# lipolski-power.net
KiCad netlist of a schematic drawn in EAGLE
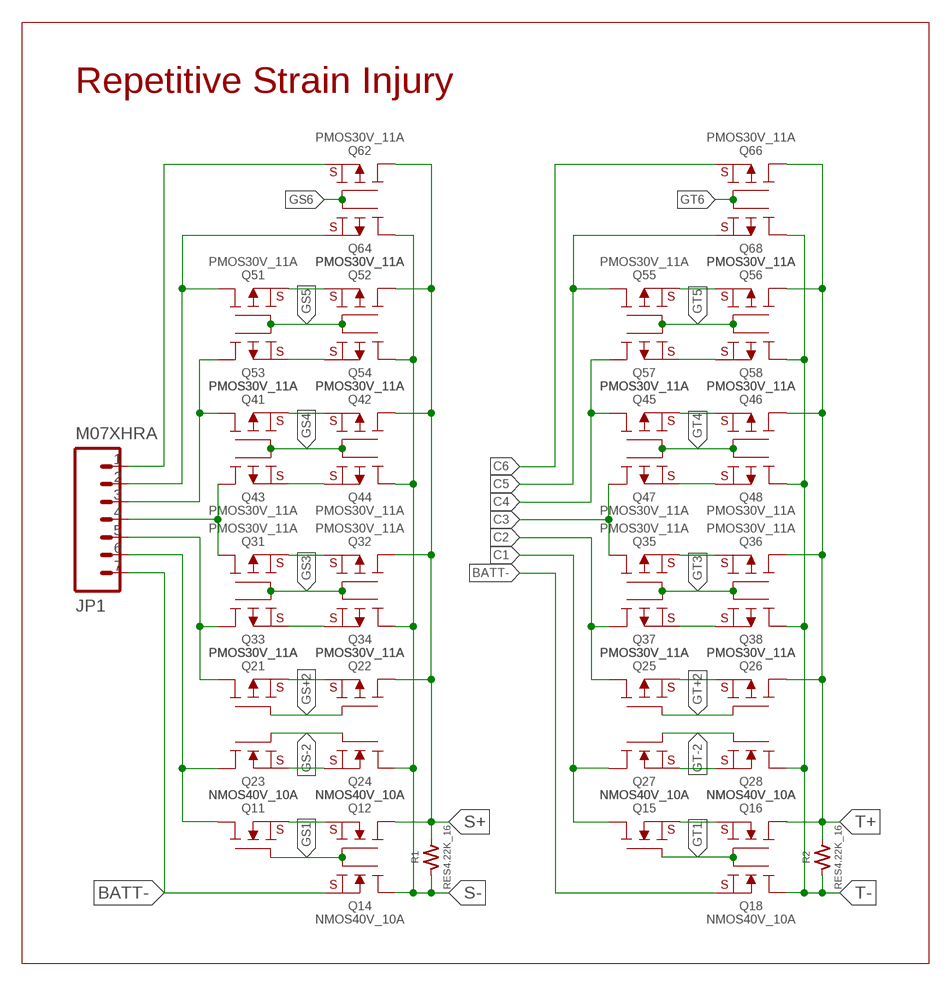
[diagram p0: schematic, sheet 1, part 1 of 2]
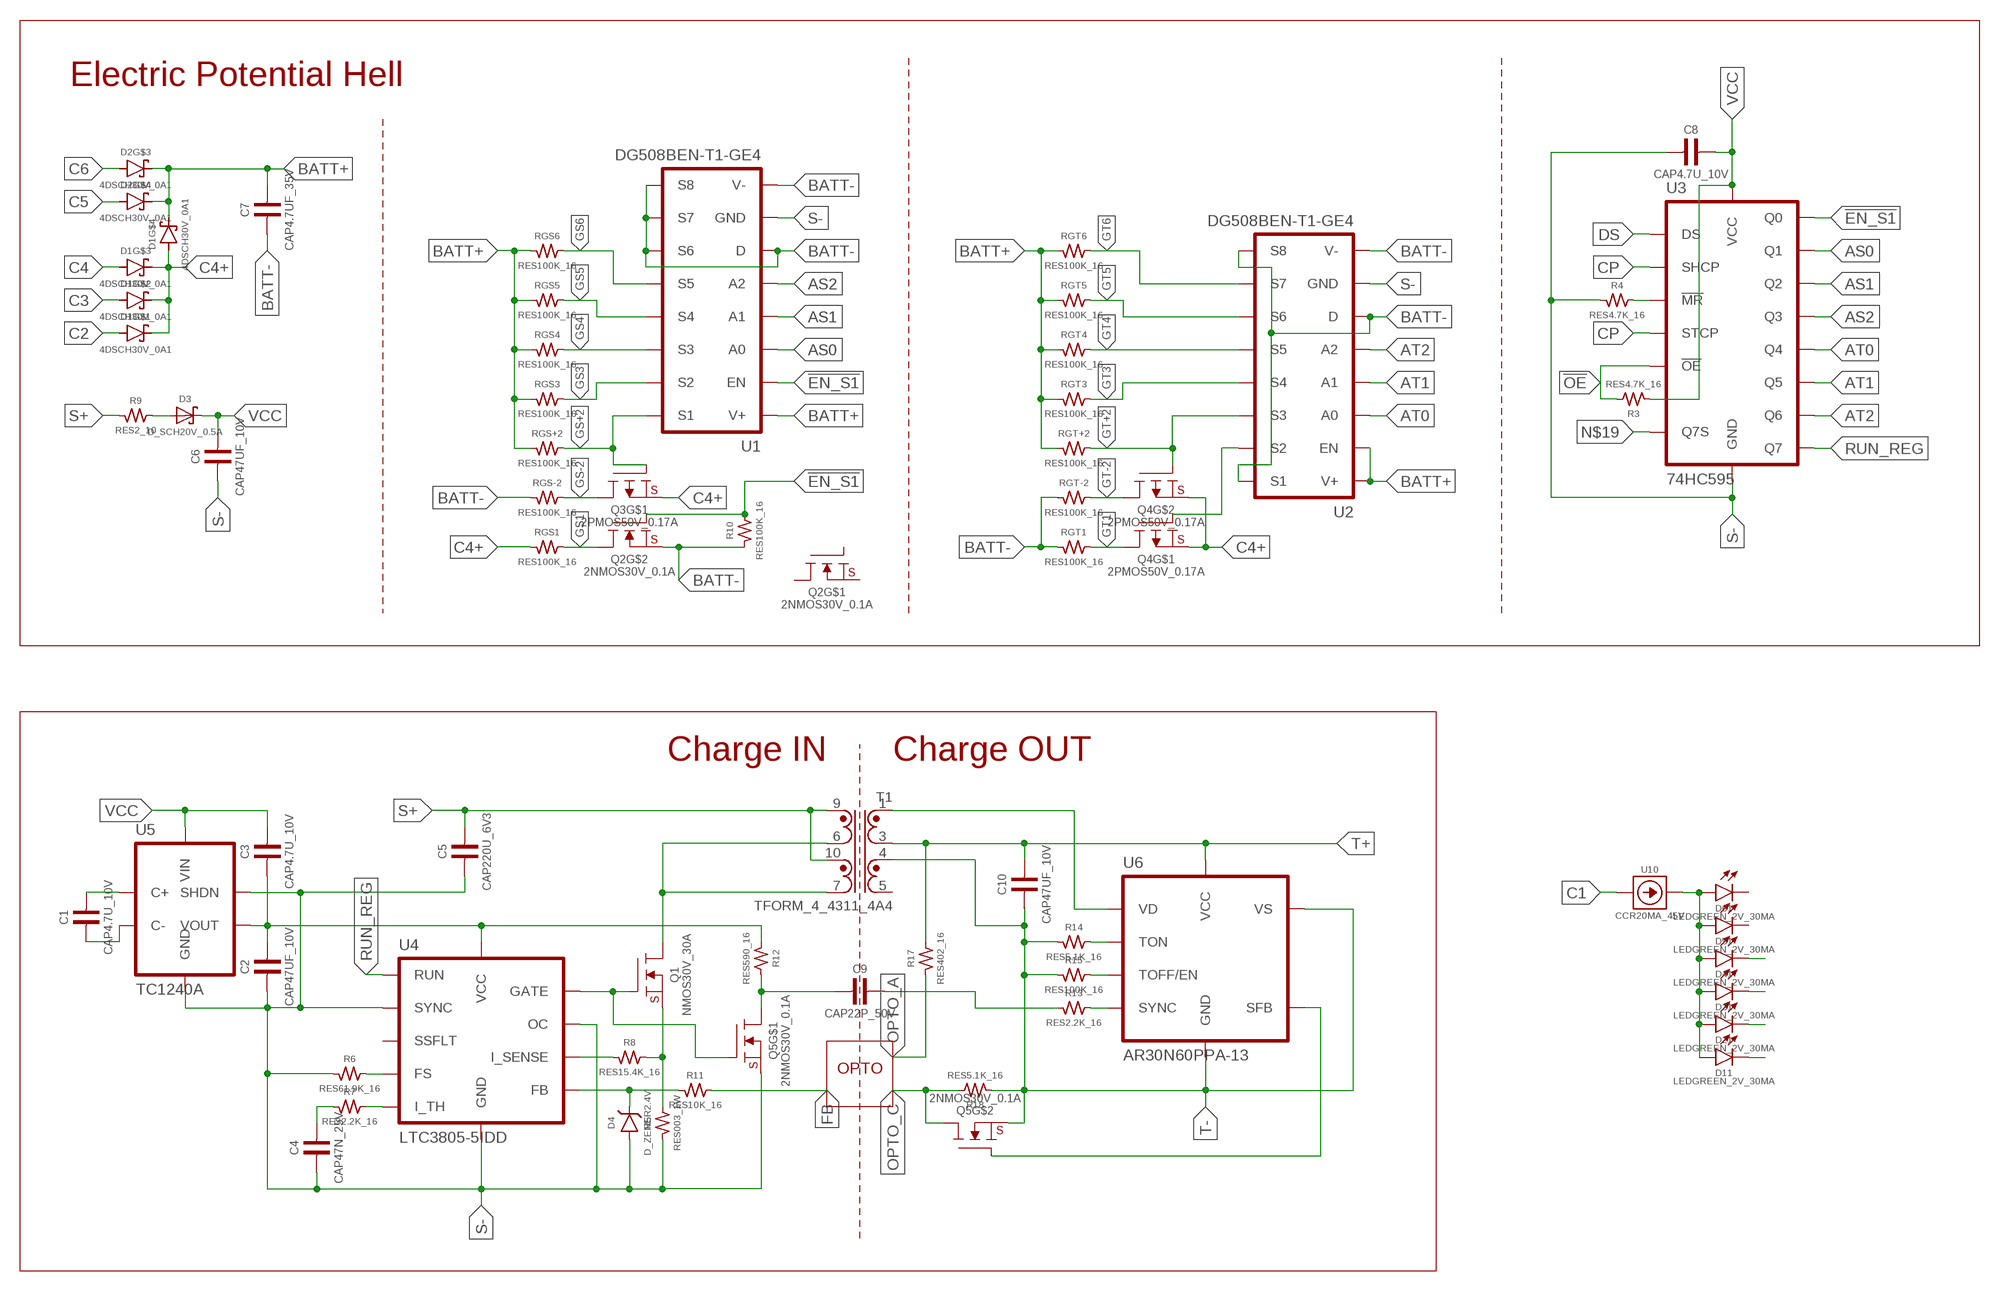
[diagram p1: schematic, sheet 1, part 2 of 2]

(export (version "E")
  (design (tool "Eeschema 10.0.6"))
  (components
    (comp (ref "C1")
      (value "CAP4.7U_10V")
      (footprint "eagle-import:0603")
      (fields
        (field (name "DIGIKEY_PART_#") "587-1441-1-ND")
        (field (name "MANUFACTURER") "Taiyo Yuden")
        (field (name "MFG_PART_#") "LMK107BJ475KA-T")
      )
      (libsource (lib "eagle-import") (part "CAP4.7U_10V"))
    )
    (comp (ref "C2")
      (value "CAP47UF_10V")
      (footprint "eagle-import:0805")
      (fields
        (field (name "DIGIKEY_PART_#") "445-8239-1-ND")
        (field (name "MANUFACTURER") "TDK Corporation")
        (field (name "MFG_PART_#") "C2012X5R1A476M125AC")
      )
      (libsource (lib "eagle-import") (part "CAP47UF_10V"))
    )
    (comp (ref "C3")
      (value "CAP4.7U_10V")
      (footprint "eagle-import:0603")
      (fields
        (field (name "DIGIKEY_PART_#") "587-1441-1-ND")
        (field (name "MANUFACTURER") "Taiyo Yuden")
        (field (name "MFG_PART_#") "LMK107BJ475KA-T")
      )
      (libsource (lib "eagle-import") (part "CAP4.7U_10V"))
    )
    (comp (ref "C4")
      (value "CAP47N_25V")
      (footprint "eagle-import:0402")
      (fields
        (field (name "DIGIKEY_PART_#") "490-3254-1-ND")
        (field (name "MANUFACTURER") "Murata Electronics North America")
        (field (name "MFG_PART_#") "GRM155R71E473KA88D")
      )
      (libsource (lib "eagle-import") (part "CAP47N_25V"))
    )
    (comp (ref "C5")
      (value "CAP220U_6V3")
      (footprint "eagle-import:1210")
      (fields
        (field (name "DIGIKEY_PART_#") "1276-3375-1-ND")
        (field (name "MANUFACTURER") "Samsung Electro-Mechanics America, Inc.")
        (field (name "MFG_PART_#") "CL32A227MQVNNNE")
      )
      (libsource (lib "eagle-import") (part "CAP220U_6V3"))
    )
    (comp (ref "C6")
      (value "CAP47UF_10V")
      (footprint "eagle-import:0805")
      (fields
        (field (name "DIGIKEY_PART_#") "445-8239-1-ND")
        (field (name "MANUFACTURER") "TDK Corporation")
        (field (name "MFG_PART_#") "C2012X5R1A476M125AC")
      )
      (libsource (lib "eagle-import") (part "CAP47UF_10V"))
    )
    (comp (ref "C7")
      (value "CAP4.7UF_35V")
      (footprint "eagle-import:0603")
      (fields
        (field (name "DIGIKEY_PART_#") "445-11301-1-ND")
        (field (name "MANUFACTURER") "TDK Corporation")
        (field (name "MFG_PART_#") "C1608JB1V475K080AC")
      )
      (libsource (lib "eagle-import") (part "CAP4.7UF_35V"))
    )
    (comp (ref "C8")
      (value "CAP4.7U_10V")
      (footprint "eagle-import:0603")
      (fields
        (field (name "DIGIKEY_PART_#") "587-1441-1-ND")
        (field (name "MANUFACTURER") "Taiyo Yuden")
        (field (name "MFG_PART_#") "LMK107BJ475KA-T")
      )
      (libsource (lib "eagle-import") (part "CAP4.7U_10V"))
    )
    (comp (ref "C9")
      (value "CAP22P_50V")
      (footprint "eagle-import:0402")
      (fields
        (field (name "DIGIKEY_PART_#") "478-1074-1-ND")
        (field (name "MANUFACTURER") "AVX Corporation")
        (field (name "MFG_PART_#") "04025A220JAT2A")
      )
      (libsource (lib "eagle-import") (part "CAP22P_50V"))
    )
    (comp (ref "C10")
      (value "CAP47UF_10V")
      (footprint "eagle-import:0805")
      (fields
        (field (name "DIGIKEY_PART_#") "445-8239-1-ND")
        (field (name "MANUFACTURER") "TDK Corporation")
        (field (name "MFG_PART_#") "C2012X5R1A476M125AC")
      )
      (libsource (lib "eagle-import") (part "CAP47UF_10V"))
    )
    (comp (ref "D1")
      (value "4DSCH30V_0A1")
      (footprint "eagle-import:8-HMD")
      (fields
        (field (name "DIGIKEY_PART_#") "RB521ZS8A30TE61CT-ND")
        (field (name "MANUFACTURER") "Rohm Semiconductor")
        (field (name "MFG_PART_#") "RB521ZS8A30TE61")
      )
      (libsource (lib "eagle-import") (part "4DSCH30V_0A1"))
    )
    (comp (ref "D2")
      (value "4DSCH30V_0A1")
      (footprint "eagle-import:8-HMD")
      (fields
        (field (name "DIGIKEY_PART_#") "RB521ZS8A30TE61CT-ND")
        (field (name "MANUFACTURER") "Rohm Semiconductor")
        (field (name "MFG_PART_#") "RB521ZS8A30TE61")
      )
      (libsource (lib "eagle-import") (part "4DSCH30V_0A1"))
    )
    (comp (ref "D3")
      (value "D_SCH20V_0.5A")
      (footprint "eagle-import:SOD523+")
      (fields
        (field (name "DIGIKEY_PART_#") "NSR0520V2T1GOSCT-ND")
        (field (name "MANUFACTURER") "ON Semiconductor")
        (field (name "MFG_PART_#") "NSR0520V2T1G")
      )
      (libsource (lib "eagle-import") (part "D_SCH20V_0.5A"))
    )
    (comp (ref "D4")
      (value "D_ZENER2.4V")
      (footprint "eagle-import:SOD523+")
      (fields
        (field (name "DIGIKEY_PART_#") "BZT585B2V4T-7DICT-ND")
        (field (name "MANUFACTURER") "Diodes Incorporated")
        (field (name "MFG_PART_#") "BZT585B2V4T-7")
      )
      (libsource (lib "eagle-import") (part "D_ZENER2.4V"))
    )
    (comp (ref "D11")
      (value "LEDGREEN_2V_30MA")
      (footprint "eagle-import:0603+")
      (fields
        (field (name "DIGIKEY_PART_#") "160-1435-1-ND")
        (field (name "MANUFACTURER") "Lite-On Inc.")
        (field (name "MFG_PART_#") "LTST-C190KGKT")
      )
      (libsource (lib "eagle-import") (part "LEDGREEN_2V_30MA"))
    )
    (comp (ref "D21")
      (value "LEDGREEN_2V_30MA")
      (footprint "eagle-import:0603+")
      (fields
        (field (name "DIGIKEY_PART_#") "160-1435-1-ND")
        (field (name "MANUFACTURER") "Lite-On Inc.")
        (field (name "MFG_PART_#") "LTST-C190KGKT")
      )
      (libsource (lib "eagle-import") (part "LEDGREEN_2V_30MA"))
    )
    (comp (ref "D31")
      (value "LEDGREEN_2V_30MA")
      (footprint "eagle-import:0603+")
      (fields
        (field (name "DIGIKEY_PART_#") "160-1435-1-ND")
        (field (name "MANUFACTURER") "Lite-On Inc.")
        (field (name "MFG_PART_#") "LTST-C190KGKT")
      )
      (libsource (lib "eagle-import") (part "LEDGREEN_2V_30MA"))
    )
    (comp (ref "D41")
      (value "LEDGREEN_2V_30MA")
      (footprint "eagle-import:0603+")
      (fields
        (field (name "DIGIKEY_PART_#") "160-1435-1-ND")
        (field (name "MANUFACTURER") "Lite-On Inc.")
        (field (name "MFG_PART_#") "LTST-C190KGKT")
      )
      (libsource (lib "eagle-import") (part "LEDGREEN_2V_30MA"))
    )
    (comp (ref "D51")
      (value "LEDGREEN_2V_30MA")
      (footprint "eagle-import:0603+")
      (fields
        (field (name "DIGIKEY_PART_#") "160-1435-1-ND")
        (field (name "MANUFACTURER") "Lite-On Inc.")
        (field (name "MFG_PART_#") "LTST-C190KGKT")
      )
      (libsource (lib "eagle-import") (part "LEDGREEN_2V_30MA"))
    )
    (comp (ref "D61")
      (value "LEDGREEN_2V_30MA")
      (footprint "eagle-import:0603+")
      (fields
        (field (name "DIGIKEY_PART_#") "160-1435-1-ND")
        (field (name "MANUFACTURER") "Lite-On Inc.")
        (field (name "MFG_PART_#") "LTST-C190KGKT")
      )
      (libsource (lib "eagle-import") (part "LEDGREEN_2V_30MA"))
    )
    (comp (ref "JP1")
      (value "M07XHRA")
      (footprint "eagle-import:XH07-RA")
      (fields
        (field (name "DIGIKEY_PART_#") "455-2240-ND")
        (field (name "MANUFACTURER") "JST Sales America Inc.")
        (field (name "MFG_PART_#") "S7B-XH-A(LF)(SN)")
      )
      (libsource (lib "eagle-import") (part "M07XHRA"))
    )
    (comp (ref "Q1")
      (value "NMOS30V_30A")
      (footprint "eagle-import:8-POWERWDFN")
      (fields
        (field (name "DIGIKEY_PART_#") "FDMC8010ET30CT-ND")
        (field (name "MANUFACTURER") "Fairchild Semiconductor")
        (field (name "MFG_PART_#") "FDMC8010ET30")
      )
      (libsource (lib "eagle-import") (part "NMOS30V_30A"))
    )
    (comp (ref "Q2")
      (value "2NMOS30V_0.1A")
      (footprint "eagle-import:SOT-666")
      (fields
        (field (name "DIGIKEY_PART_#") "FC6943010RCT-ND")
        (field (name "MANUFACTURER") "Panasonic Electronic Components")
        (field (name "MFG_PART_#") "FC6943010R")
      )
      (libsource (lib "eagle-import") (part "2NMOS30V_0.1A"))
    )
    (comp (ref "Q3")
      (value "2PMOS50V_0.17A")
      (footprint "eagle-import:SOT-666")
      (fields
        (field (name "DIGIKEY_PART_#") "568-10474-1-ND")
        (field (name "MANUFACTURER") "NXP Semiconductors")
        (field (name "MFG_PART_#") "BSS84AKV,115")
      )
      (libsource (lib "eagle-import") (part "2PMOS50V_0.17A"))
    )
    (comp (ref "Q4")
      (value "2PMOS50V_0.17A")
      (footprint "eagle-import:SOT-666")
      (fields
        (field (name "DIGIKEY_PART_#") "568-10474-1-ND")
        (field (name "MANUFACTURER") "NXP Semiconductors")
        (field (name "MFG_PART_#") "BSS84AKV,115")
      )
      (libsource (lib "eagle-import") (part "2PMOS50V_0.17A"))
    )
    (comp (ref "Q5")
      (value "2NMOS30V_0.1A")
      (footprint "eagle-import:SOT-666")
      (fields
        (field (name "DIGIKEY_PART_#") "FC6943010RCT-ND")
        (field (name "MANUFACTURER") "Panasonic Electronic Components")
        (field (name "MFG_PART_#") "FC6943010R")
      )
      (libsource (lib "eagle-import") (part "2NMOS30V_0.1A"))
    )
    (comp (ref "Q11")
      (value "NMOS40V_10A")
      (footprint "eagle-import:6-POWERWDFN")
      (fields
        (field (name "DIGIKEY_PART_#") "FDMA7670CT-ND")
        (field (name "MANUFACTURER") "Fairchild Semiconductor")
        (field (name "MFG_PART_#") "FDMA7670")
      )
      (libsource (lib "eagle-import") (part "NMOS40V_10A"))
    )
    (comp (ref "Q12")
      (value "NMOS40V_10A")
      (footprint "eagle-import:6-POWERWDFN")
      (fields
        (field (name "DIGIKEY_PART_#") "FDMA7670CT-ND")
        (field (name "MANUFACTURER") "Fairchild Semiconductor")
        (field (name "MFG_PART_#") "FDMA7670")
      )
      (libsource (lib "eagle-import") (part "NMOS40V_10A"))
    )
    (comp (ref "Q14")
      (value "NMOS40V_10A")
      (footprint "eagle-import:6-POWERWDFN")
      (fields
        (field (name "DIGIKEY_PART_#") "FDMA7670CT-ND")
        (field (name "MANUFACTURER") "Fairchild Semiconductor")
        (field (name "MFG_PART_#") "FDMA7670")
      )
      (libsource (lib "eagle-import") (part "NMOS40V_10A"))
    )
    (comp (ref "Q15")
      (value "NMOS40V_10A")
      (footprint "eagle-import:6-POWERWDFN")
      (fields
        (field (name "DIGIKEY_PART_#") "FDMA7670CT-ND")
        (field (name "MANUFACTURER") "Fairchild Semiconductor")
        (field (name "MFG_PART_#") "FDMA7670")
      )
      (libsource (lib "eagle-import") (part "NMOS40V_10A"))
    )
    (comp (ref "Q16")
      (value "NMOS40V_10A")
      (footprint "eagle-import:6-POWERWDFN")
      (fields
        (field (name "DIGIKEY_PART_#") "FDMA7670CT-ND")
        (field (name "MANUFACTURER") "Fairchild Semiconductor")
        (field (name "MFG_PART_#") "FDMA7670")
      )
      (libsource (lib "eagle-import") (part "NMOS40V_10A"))
    )
    (comp (ref "Q18")
      (value "NMOS40V_10A")
      (footprint "eagle-import:6-POWERWDFN")
      (fields
        (field (name "DIGIKEY_PART_#") "FDMA7670CT-ND")
        (field (name "MANUFACTURER") "Fairchild Semiconductor")
        (field (name "MFG_PART_#") "FDMA7670")
      )
      (libsource (lib "eagle-import") (part "NMOS40V_10A"))
    )
    (comp (ref "Q21")
      (value "PMOS30V_11A")
      (footprint "eagle-import:6-POWERWDFN")
      (fields
        (field (name "DIGIKEY_PART_#") "FDMA6676PZCT-ND")
        (field (name "MANUFACTURER") "Fairchild Semiconductor")
        (field (name "MFG_PART_#") "FDMA6676PZ")
      )
      (libsource (lib "eagle-import") (part "PMOS30V_11A"))
    )
    (comp (ref "Q22")
      (value "PMOS30V_11A")
      (footprint "eagle-import:6-POWERWDFN")
      (fields
        (field (name "DIGIKEY_PART_#") "FDMA6676PZCT-ND")
        (field (name "MANUFACTURER") "Fairchild Semiconductor")
        (field (name "MFG_PART_#") "FDMA6676PZ")
      )
      (libsource (lib "eagle-import") (part "PMOS30V_11A"))
    )
    (comp (ref "Q23")
      (value "NMOS40V_10A")
      (footprint "eagle-import:6-POWERWDFN")
      (fields
        (field (name "DIGIKEY_PART_#") "FDMA7670CT-ND")
        (field (name "MANUFACTURER") "Fairchild Semiconductor")
        (field (name "MFG_PART_#") "FDMA7670")
      )
      (libsource (lib "eagle-import") (part "NMOS40V_10A"))
    )
    (comp (ref "Q24")
      (value "NMOS40V_10A")
      (footprint "eagle-import:6-POWERWDFN")
      (fields
        (field (name "DIGIKEY_PART_#") "FDMA7670CT-ND")
        (field (name "MANUFACTURER") "Fairchild Semiconductor")
        (field (name "MFG_PART_#") "FDMA7670")
      )
      (libsource (lib "eagle-import") (part "NMOS40V_10A"))
    )
    (comp (ref "Q25")
      (value "PMOS30V_11A")
      (footprint "eagle-import:6-POWERWDFN")
      (fields
        (field (name "DIGIKEY_PART_#") "FDMA6676PZCT-ND")
        (field (name "MANUFACTURER") "Fairchild Semiconductor")
        (field (name "MFG_PART_#") "FDMA6676PZ")
      )
      (libsource (lib "eagle-import") (part "PMOS30V_11A"))
    )
    (comp (ref "Q26")
      (value "PMOS30V_11A")
      (footprint "eagle-import:6-POWERWDFN")
      (fields
        (field (name "DIGIKEY_PART_#") "FDMA6676PZCT-ND")
        (field (name "MANUFACTURER") "Fairchild Semiconductor")
        (field (name "MFG_PART_#") "FDMA6676PZ")
      )
      (libsource (lib "eagle-import") (part "PMOS30V_11A"))
    )
    (comp (ref "Q27")
      (value "NMOS40V_10A")
      (footprint "eagle-import:6-POWERWDFN")
      (fields
        (field (name "DIGIKEY_PART_#") "FDMA7670CT-ND")
        (field (name "MANUFACTURER") "Fairchild Semiconductor")
        (field (name "MFG_PART_#") "FDMA7670")
      )
      (libsource (lib "eagle-import") (part "NMOS40V_10A"))
    )
    (comp (ref "Q28")
      (value "NMOS40V_10A")
      (footprint "eagle-import:6-POWERWDFN")
      (fields
        (field (name "DIGIKEY_PART_#") "FDMA7670CT-ND")
        (field (name "MANUFACTURER") "Fairchild Semiconductor")
        (field (name "MFG_PART_#") "FDMA7670")
      )
      (libsource (lib "eagle-import") (part "NMOS40V_10A"))
    )
    (comp (ref "Q31")
      (value "PMOS30V_11A")
      (footprint "eagle-import:6-POWERWDFN")
      (fields
        (field (name "DIGIKEY_PART_#") "FDMA6676PZCT-ND")
        (field (name "MANUFACTURER") "Fairchild Semiconductor")
        (field (name "MFG_PART_#") "FDMA6676PZ")
      )
      (libsource (lib "eagle-import") (part "PMOS30V_11A"))
    )
    (comp (ref "Q32")
      (value "PMOS30V_11A")
      (footprint "eagle-import:6-POWERWDFN")
      (fields
        (field (name "DIGIKEY_PART_#") "FDMA6676PZCT-ND")
        (field (name "MANUFACTURER") "Fairchild Semiconductor")
        (field (name "MFG_PART_#") "FDMA6676PZ")
      )
      (libsource (lib "eagle-import") (part "PMOS30V_11A"))
    )
    (comp (ref "Q33")
      (value "PMOS30V_11A")
      (footprint "eagle-import:6-POWERWDFN")
      (fields
        (field (name "DIGIKEY_PART_#") "FDMA6676PZCT-ND")
        (field (name "MANUFACTURER") "Fairchild Semiconductor")
        (field (name "MFG_PART_#") "FDMA6676PZ")
      )
      (libsource (lib "eagle-import") (part "PMOS30V_11A"))
    )
    (comp (ref "Q34")
      (value "PMOS30V_11A")
      (footprint "eagle-import:6-POWERWDFN")
      (fields
        (field (name "DIGIKEY_PART_#") "FDMA6676PZCT-ND")
        (field (name "MANUFACTURER") "Fairchild Semiconductor")
        (field (name "MFG_PART_#") "FDMA6676PZ")
      )
      (libsource (lib "eagle-import") (part "PMOS30V_11A"))
    )
    (comp (ref "Q35")
      (value "PMOS30V_11A")
      (footprint "eagle-import:6-POWERWDFN")
      (fields
        (field (name "DIGIKEY_PART_#") "FDMA6676PZCT-ND")
        (field (name "MANUFACTURER") "Fairchild Semiconductor")
        (field (name "MFG_PART_#") "FDMA6676PZ")
      )
      (libsource (lib "eagle-import") (part "PMOS30V_11A"))
    )
    (comp (ref "Q36")
      (value "PMOS30V_11A")
      (footprint "eagle-import:6-POWERWDFN")
      (fields
        (field (name "DIGIKEY_PART_#") "FDMA6676PZCT-ND")
        (field (name "MANUFACTURER") "Fairchild Semiconductor")
        (field (name "MFG_PART_#") "FDMA6676PZ")
      )
      (libsource (lib "eagle-import") (part "PMOS30V_11A"))
    )
    (comp (ref "Q37")
      (value "PMOS30V_11A")
      (footprint "eagle-import:6-POWERWDFN")
      (fields
        (field (name "DIGIKEY_PART_#") "FDMA6676PZCT-ND")
        (field (name "MANUFACTURER") "Fairchild Semiconductor")
        (field (name "MFG_PART_#") "FDMA6676PZ")
      )
      (libsource (lib "eagle-import") (part "PMOS30V_11A"))
    )
    (comp (ref "Q38")
      (value "PMOS30V_11A")
      (footprint "eagle-import:6-POWERWDFN")
      (fields
        (field (name "DIGIKEY_PART_#") "FDMA6676PZCT-ND")
        (field (name "MANUFACTURER") "Fairchild Semiconductor")
        (field (name "MFG_PART_#") "FDMA6676PZ")
      )
      (libsource (lib "eagle-import") (part "PMOS30V_11A"))
    )
    (comp (ref "Q41")
      (value "PMOS30V_11A")
      (footprint "eagle-import:6-POWERWDFN")
      (fields
        (field (name "DIGIKEY_PART_#") "FDMA6676PZCT-ND")
        (field (name "MANUFACTURER") "Fairchild Semiconductor")
        (field (name "MFG_PART_#") "FDMA6676PZ")
      )
      (libsource (lib "eagle-import") (part "PMOS30V_11A"))
    )
    (comp (ref "Q42")
      (value "PMOS30V_11A")
      (footprint "eagle-import:6-POWERWDFN")
      (fields
        (field (name "DIGIKEY_PART_#") "FDMA6676PZCT-ND")
        (field (name "MANUFACTURER") "Fairchild Semiconductor")
        (field (name "MFG_PART_#") "FDMA6676PZ")
      )
      (libsource (lib "eagle-import") (part "PMOS30V_11A"))
    )
    (comp (ref "Q43")
      (value "PMOS30V_11A")
      (footprint "eagle-import:6-POWERWDFN")
      (fields
        (field (name "DIGIKEY_PART_#") "FDMA6676PZCT-ND")
        (field (name "MANUFACTURER") "Fairchild Semiconductor")
        (field (name "MFG_PART_#") "FDMA6676PZ")
      )
      (libsource (lib "eagle-import") (part "PMOS30V_11A"))
    )
    (comp (ref "Q44")
      (value "PMOS30V_11A")
      (footprint "eagle-import:6-POWERWDFN")
      (fields
        (field (name "DIGIKEY_PART_#") "FDMA6676PZCT-ND")
        (field (name "MANUFACTURER") "Fairchild Semiconductor")
        (field (name "MFG_PART_#") "FDMA6676PZ")
      )
      (libsource (lib "eagle-import") (part "PMOS30V_11A"))
    )
    (comp (ref "Q45")
      (value "PMOS30V_11A")
      (footprint "eagle-import:6-POWERWDFN")
      (fields
        (field (name "DIGIKEY_PART_#") "FDMA6676PZCT-ND")
        (field (name "MANUFACTURER") "Fairchild Semiconductor")
        (field (name "MFG_PART_#") "FDMA6676PZ")
      )
      (libsource (lib "eagle-import") (part "PMOS30V_11A"))
    )
    (comp (ref "Q46")
      (value "PMOS30V_11A")
      (footprint "eagle-import:6-POWERWDFN")
      (fields
        (field (name "DIGIKEY_PART_#") "FDMA6676PZCT-ND")
        (field (name "MANUFACTURER") "Fairchild Semiconductor")
        (field (name "MFG_PART_#") "FDMA6676PZ")
      )
      (libsource (lib "eagle-import") (part "PMOS30V_11A"))
    )
    (comp (ref "Q47")
      (value "PMOS30V_11A")
      (footprint "eagle-import:6-POWERWDFN")
      (fields
        (field (name "DIGIKEY_PART_#") "FDMA6676PZCT-ND")
        (field (name "MANUFACTURER") "Fairchild Semiconductor")
        (field (name "MFG_PART_#") "FDMA6676PZ")
      )
      (libsource (lib "eagle-import") (part "PMOS30V_11A"))
    )
    (comp (ref "Q48")
      (value "PMOS30V_11A")
      (footprint "eagle-import:6-POWERWDFN")
      (fields
        (field (name "DIGIKEY_PART_#") "FDMA6676PZCT-ND")
        (field (name "MANUFACTURER") "Fairchild Semiconductor")
        (field (name "MFG_PART_#") "FDMA6676PZ")
      )
      (libsource (lib "eagle-import") (part "PMOS30V_11A"))
    )
    (comp (ref "Q51")
      (value "PMOS30V_11A")
      (footprint "eagle-import:6-POWERWDFN")
      (fields
        (field (name "DIGIKEY_PART_#") "FDMA6676PZCT-ND")
        (field (name "MANUFACTURER") "Fairchild Semiconductor")
        (field (name "MFG_PART_#") "FDMA6676PZ")
      )
      (libsource (lib "eagle-import") (part "PMOS30V_11A"))
    )
    (comp (ref "Q52")
      (value "PMOS30V_11A")
      (footprint "eagle-import:6-POWERWDFN")
      (fields
        (field (name "DIGIKEY_PART_#") "FDMA6676PZCT-ND")
        (field (name "MANUFACTURER") "Fairchild Semiconductor")
        (field (name "MFG_PART_#") "FDMA6676PZ")
      )
      (libsource (lib "eagle-import") (part "PMOS30V_11A"))
    )
    (comp (ref "Q53")
      (value "PMOS30V_11A")
      (footprint "eagle-import:6-POWERWDFN")
      (fields
        (field (name "DIGIKEY_PART_#") "FDMA6676PZCT-ND")
        (field (name "MANUFACTURER") "Fairchild Semiconductor")
        (field (name "MFG_PART_#") "FDMA6676PZ")
      )
      (libsource (lib "eagle-import") (part "PMOS30V_11A"))
    )
    (comp (ref "Q54")
      (value "PMOS30V_11A")
      (footprint "eagle-import:6-POWERWDFN")
      (fields
        (field (name "DIGIKEY_PART_#") "FDMA6676PZCT-ND")
        (field (name "MANUFACTURER") "Fairchild Semiconductor")
        (field (name "MFG_PART_#") "FDMA6676PZ")
      )
      (libsource (lib "eagle-import") (part "PMOS30V_11A"))
    )
    (comp (ref "Q55")
      (value "PMOS30V_11A")
      (footprint "eagle-import:6-POWERWDFN")
      (fields
        (field (name "DIGIKEY_PART_#") "FDMA6676PZCT-ND")
        (field (name "MANUFACTURER") "Fairchild Semiconductor")
        (field (name "MFG_PART_#") "FDMA6676PZ")
      )
      (libsource (lib "eagle-import") (part "PMOS30V_11A"))
    )
    (comp (ref "Q56")
      (value "PMOS30V_11A")
      (footprint "eagle-import:6-POWERWDFN")
      (fields
        (field (name "DIGIKEY_PART_#") "FDMA6676PZCT-ND")
        (field (name "MANUFACTURER") "Fairchild Semiconductor")
        (field (name "MFG_PART_#") "FDMA6676PZ")
      )
      (libsource (lib "eagle-import") (part "PMOS30V_11A"))
    )
    (comp (ref "Q57")
      (value "PMOS30V_11A")
      (footprint "eagle-import:6-POWERWDFN")
      (fields
        (field (name "DIGIKEY_PART_#") "FDMA6676PZCT-ND")
        (field (name "MANUFACTURER") "Fairchild Semiconductor")
        (field (name "MFG_PART_#") "FDMA6676PZ")
      )
      (libsource (lib "eagle-import") (part "PMOS30V_11A"))
    )
    (comp (ref "Q58")
      (value "PMOS30V_11A")
      (footprint "eagle-import:6-POWERWDFN")
      (fields
        (field (name "DIGIKEY_PART_#") "FDMA6676PZCT-ND")
        (field (name "MANUFACTURER") "Fairchild Semiconductor")
        (field (name "MFG_PART_#") "FDMA6676PZ")
      )
      (libsource (lib "eagle-import") (part "PMOS30V_11A"))
    )
    (comp (ref "Q62")
      (value "PMOS30V_11A")
      (footprint "eagle-import:6-POWERWDFN")
      (fields
        (field (name "DIGIKEY_PART_#") "FDMA6676PZCT-ND")
        (field (name "MANUFACTURER") "Fairchild Semiconductor")
        (field (name "MFG_PART_#") "FDMA6676PZ")
      )
      (libsource (lib "eagle-import") (part "PMOS30V_11A"))
    )
    (comp (ref "Q64")
      (value "PMOS30V_11A")
      (footprint "eagle-import:6-POWERWDFN")
      (fields
        (field (name "DIGIKEY_PART_#") "FDMA6676PZCT-ND")
        (field (name "MANUFACTURER") "Fairchild Semiconductor")
        (field (name "MFG_PART_#") "FDMA6676PZ")
      )
      (libsource (lib "eagle-import") (part "PMOS30V_11A"))
    )
    (comp (ref "Q66")
      (value "PMOS30V_11A")
      (footprint "eagle-import:6-POWERWDFN")
      (fields
        (field (name "DIGIKEY_PART_#") "FDMA6676PZCT-ND")
        (field (name "MANUFACTURER") "Fairchild Semiconductor")
        (field (name "MFG_PART_#") "FDMA6676PZ")
      )
      (libsource (lib "eagle-import") (part "PMOS30V_11A"))
    )
    (comp (ref "Q68")
      (value "PMOS30V_11A")
      (footprint "eagle-import:6-POWERWDFN")
      (fields
        (field (name "DIGIKEY_PART_#") "FDMA6676PZCT-ND")
        (field (name "MANUFACTURER") "Fairchild Semiconductor")
        (field (name "MFG_PART_#") "FDMA6676PZ")
      )
      (libsource (lib "eagle-import") (part "PMOS30V_11A"))
    )
    (comp (ref "R1")
      (value "RES4.22K_16")
      (footprint "eagle-import:0402")
      (fields
        (field (name "DIGIKEY_PART_#") "541-4.22KLCT-ND")
        (field (name "MANUFACTURER") "Vishay Dale")
        (field (name "MFG_PART_#") "CRCW04024K22FKED")
      )
      (libsource (lib "eagle-import") (part "RES4.22K_16"))
    )
    (comp (ref "R2")
      (value "RES4.22K_16")
      (footprint "eagle-import:0402")
      (fields
        (field (name "DIGIKEY_PART_#") "541-4.22KLCT-ND")
        (field (name "MANUFACTURER") "Vishay Dale")
        (field (name "MFG_PART_#") "CRCW04024K22FKED")
      )
      (libsource (lib "eagle-import") (part "RES4.22K_16"))
    )
    (comp (ref "R3")
      (value "RES4.7K_16")
      (footprint "eagle-import:0402")
      (fields
        (field (name "DIGIKEY_PART_#") "541-4.70KLCT-ND")
        (field (name "MANUFACTURER") "Vishay Dale")
        (field (name "MFG_PART_#") "CRCW04024K70FKED")
      )
      (libsource (lib "eagle-import") (part "RES4.7K_16"))
    )
    (comp (ref "R4")
      (value "RES4.7K_16")
      (footprint "eagle-import:0402")
      (fields
        (field (name "DIGIKEY_PART_#") "541-4.70KLCT-ND")
        (field (name "MANUFACTURER") "Vishay Dale")
        (field (name "MFG_PART_#") "CRCW04024K70FKED")
      )
      (libsource (lib "eagle-import") (part "RES4.7K_16"))
    )
    (comp (ref "R5")
      (value "RES003_1W")
      (footprint "eagle-import:1206")
      (fields
        (field (name "DIGIKEY_PART_#") "CSNL1206FT3L00CT-ND")
        (field (name "MANUFACTURER") "Stackpole Electronics Inc.")
        (field (name "MFG_PART_#") "CSNL1206FT3L00")
      )
      (libsource (lib "eagle-import") (part "RES003_1W"))
    )
    (comp (ref "R6")
      (value "RES61.9K_16")
      (footprint "eagle-import:0402")
      (fields
        (field (name "DIGIKEY_PART_#") "541-61.9KLCT-ND")
        (field (name "MANUFACTURER") "Vishay Dale")
        (field (name "MFG_PART_#") "CRCW040261K9FKED")
      )
      (libsource (lib "eagle-import") (part "RES61.9K_16"))
    )
    (comp (ref "R7")
      (value "RES2.2K_16")
      (footprint "eagle-import:0402")
      (fields
        (field (name "DIGIKEY_PART_#") "541-2.20KLCT-ND")
        (field (name "MANUFACTURER") "Vishay Dale")
        (field (name "MFG_PART_#") "CRCW04022K20FKED")
      )
      (libsource (lib "eagle-import") (part "RES2.2K_16"))
    )
    (comp (ref "R8")
      (value "RES15.4K_16")
      (footprint "eagle-import:0402")
      (fields
        (field (name "DIGIKEY_PART_#") "541-15.4KLCT-ND")
        (field (name "MANUFACTURER") "Vishay Dale")
        (field (name "MFG_PART_#") "CRCW040215K4FKED")
      )
      (libsource (lib "eagle-import") (part "RES15.4K_16"))
    )
    (comp (ref "R9")
      (value "RES2_10")
      (footprint "eagle-import:0603")
      (fields
        (field (name "DIGIKEY_PART_#") "311-2.00HRCT-ND")
        (field (name "MANUFACTURER") "Yageo")
        (field (name "MFG_PART_#") "RC0603FR-072RL")
      )
      (libsource (lib "eagle-import") (part "RES2_10"))
    )
    (comp (ref "R10")
      (value "RES100K_16")
      (footprint "eagle-import:0402")
      (fields
        (field (name "DIGIKEY_PART_#") "541-100KLCT-ND")
        (field (name "MANUFACTURER") "Vishay Dale")
        (field (name "MFG_PART_#") "CRCW0402100KFKED")
      )
      (libsource (lib "eagle-import") (part "RES100K_16"))
    )
    (comp (ref "R11")
      (value "RES10K_16")
      (footprint "eagle-import:0402")
      (fields
        (field (name "DIGIKEY_PART_#") "541-10.0KLCT-ND")
        (field (name "MANUFACTURER") "Vishay Dale")
        (field (name "MFG_PART_#") "CRCW040210K0FKED")
      )
      (libsource (lib "eagle-import") (part "RES10K_16"))
    )
    (comp (ref "R12")
      (value "RES590_16")
      (footprint "eagle-import:0402")
      (fields
        (field (name "DIGIKEY_PART_#") "541-590LCT-ND")
        (field (name "MANUFACTURER") "Vishay Dale")
        (field (name "MFG_PART_#") "CRCW0402590RFKED")
      )
      (libsource (lib "eagle-import") (part "RES590_16"))
    )
    (comp (ref "R13")
      (value "RES2.2K_16")
      (footprint "eagle-import:0402")
      (fields
        (field (name "DIGIKEY_PART_#") "541-2.20KLCT-ND")
        (field (name "MANUFACTURER") "Vishay Dale")
        (field (name "MFG_PART_#") "CRCW04022K20FKED")
      )
      (libsource (lib "eagle-import") (part "RES2.2K_16"))
    )
    (comp (ref "R14")
      (value "RES5.1K_16")
      (footprint "eagle-import:0402")
      (fields
        (field (name "DIGIKEY_PART_#") "541-5.10KLCT-ND")
        (field (name "MANUFACTURER") "Vishay Dale")
        (field (name "MFG_PART_#") "CRCW04025K10FKED")
      )
      (libsource (lib "eagle-import") (part "RES5.1K_16"))
    )
    (comp (ref "R15")
      (value "RES100K_16")
      (footprint "eagle-import:0402")
      (fields
        (field (name "DIGIKEY_PART_#") "541-100KLCT-ND")
        (field (name "MANUFACTURER") "Vishay Dale")
        (field (name "MFG_PART_#") "CRCW0402100KFKED")
      )
      (libsource (lib "eagle-import") (part "RES100K_16"))
    )
    (comp (ref "R17")
      (value "RES402_16")
      (footprint "eagle-import:0402")
      (fields
        (field (name "DIGIKEY_PART_#") "541-402LCT-ND")
        (field (name "MANUFACTURER") "Vishay Dale")
        (field (name "MFG_PART_#") "CRCW0402402RFKED")
      )
      (libsource (lib "eagle-import") (part "RES402_16"))
    )
    (comp (ref "R18")
      (value "RES5.1K_16")
      (footprint "eagle-import:0402")
      (fields
        (field (name "DIGIKEY_PART_#") "541-5.10KLCT-ND")
        (field (name "MANUFACTURER") "Vishay Dale")
        (field (name "MFG_PART_#") "CRCW04025K10FKED")
      )
      (libsource (lib "eagle-import") (part "RES5.1K_16"))
    )
    (comp (ref "RGS+2")
      (value "RES100K_16")
      (footprint "eagle-import:0402")
      (fields
        (field (name "DIGIKEY_PART_#") "541-100KLCT-ND")
        (field (name "MANUFACTURER") "Vishay Dale")
        (field (name "MFG_PART_#") "CRCW0402100KFKED")
      )
      (libsource (lib "eagle-import") (part "RES100K_16"))
    )
    (comp (ref "RGS-2")
      (value "RES100K_16")
      (footprint "eagle-import:0402")
      (fields
        (field (name "DIGIKEY_PART_#") "541-100KLCT-ND")
        (field (name "MANUFACTURER") "Vishay Dale")
        (field (name "MFG_PART_#") "CRCW0402100KFKED")
      )
      (libsource (lib "eagle-import") (part "RES100K_16"))
    )
    (comp (ref "RGS1")
      (value "RES100K_16")
      (footprint "eagle-import:0402")
      (fields
        (field (name "DIGIKEY_PART_#") "541-100KLCT-ND")
        (field (name "MANUFACTURER") "Vishay Dale")
        (field (name "MFG_PART_#") "CRCW0402100KFKED")
      )
      (libsource (lib "eagle-import") (part "RES100K_16"))
    )
    (comp (ref "RGS3")
      (value "RES100K_16")
      (footprint "eagle-import:0402")
      (fields
        (field (name "DIGIKEY_PART_#") "541-100KLCT-ND")
        (field (name "MANUFACTURER") "Vishay Dale")
        (field (name "MFG_PART_#") "CRCW0402100KFKED")
      )
      (libsource (lib "eagle-import") (part "RES100K_16"))
    )
    (comp (ref "RGS4")
      (value "RES100K_16")
      (footprint "eagle-import:0402")
      (fields
        (field (name "DIGIKEY_PART_#") "541-100KLCT-ND")
        (field (name "MANUFACTURER") "Vishay Dale")
        (field (name "MFG_PART_#") "CRCW0402100KFKED")
      )
      (libsource (lib "eagle-import") (part "RES100K_16"))
    )
    (comp (ref "RGS5")
      (value "RES100K_16")
      (footprint "eagle-import:0402")
      (fields
        (field (name "DIGIKEY_PART_#") "541-100KLCT-ND")
        (field (name "MANUFACTURER") "Vishay Dale")
        (field (name "MFG_PART_#") "CRCW0402100KFKED")
      )
      (libsource (lib "eagle-import") (part "RES100K_16"))
    )
    (comp (ref "RGS6")
      (value "RES100K_16")
      (footprint "eagle-import:0402")
      (fields
        (field (name "DIGIKEY_PART_#") "541-100KLCT-ND")
        (field (name "MANUFACTURER") "Vishay Dale")
        (field (name "MFG_PART_#") "CRCW0402100KFKED")
      )
      (libsource (lib "eagle-import") (part "RES100K_16"))
    )
    (comp (ref "RGT+2")
      (value "RES100K_16")
      (footprint "eagle-import:0402")
      (fields
        (field (name "DIGIKEY_PART_#") "541-100KLCT-ND")
        (field (name "MANUFACTURER") "Vishay Dale")
        (field (name "MFG_PART_#") "CRCW0402100KFKED")
      )
      (libsource (lib "eagle-import") (part "RES100K_16"))
    )
    (comp (ref "RGT-2")
      (value "RES100K_16")
      (footprint "eagle-import:0402")
      (fields
        (field (name "DIGIKEY_PART_#") "541-100KLCT-ND")
        (field (name "MANUFACTURER") "Vishay Dale")
        (field (name "MFG_PART_#") "CRCW0402100KFKED")
      )
      (libsource (lib "eagle-import") (part "RES100K_16"))
    )
    (comp (ref "RGT1")
      (value "RES100K_16")
      (footprint "eagle-import:0402")
      (fields
        (field (name "DIGIKEY_PART_#") "541-100KLCT-ND")
        (field (name "MANUFACTURER") "Vishay Dale")
        (field (name "MFG_PART_#") "CRCW0402100KFKED")
      )
      (libsource (lib "eagle-import") (part "RES100K_16"))
    )
    (comp (ref "RGT3")
      (value "RES100K_16")
      (footprint "eagle-import:0402")
      (fields
        (field (name "DIGIKEY_PART_#") "541-100KLCT-ND")
        (field (name "MANUFACTURER") "Vishay Dale")
        (field (name "MFG_PART_#") "CRCW0402100KFKED")
      )
      (libsource (lib "eagle-import") (part "RES100K_16"))
    )
    (comp (ref "RGT4")
      (value "RES100K_16")
      (footprint "eagle-import:0402")
      (fields
        (field (name "DIGIKEY_PART_#") "541-100KLCT-ND")
        (field (name "MANUFACTURER") "Vishay Dale")
        (field (name "MFG_PART_#") "CRCW0402100KFKED")
      )
      (libsource (lib "eagle-import") (part "RES100K_16"))
    )
    (comp (ref "RGT5")
      (value "RES100K_16")
      (footprint "eagle-import:0402")
      (fields
        (field (name "DIGIKEY_PART_#") "541-100KLCT-ND")
        (field (name "MANUFACTURER") "Vishay Dale")
        (field (name "MFG_PART_#") "CRCW0402100KFKED")
      )
      (libsource (lib "eagle-import") (part "RES100K_16"))
    )
    (comp (ref "RGT6")
      (value "RES100K_16")
      (footprint "eagle-import:0402")
      (fields
        (field (name "DIGIKEY_PART_#") "541-100KLCT-ND")
        (field (name "MANUFACTURER") "Vishay Dale")
        (field (name "MFG_PART_#") "CRCW0402100KFKED")
      )
      (libsource (lib "eagle-import") (part "RES100K_16"))
    )
    (comp (ref "T1")
      (value "TFORM_4_4311_4A4")
      (footprint "eagle-import:EPQ13")
      (fields
        (field (name "DIGIKEY_PART_#") "732-6198-1-ND")
        (field (name "MANUFACTURER") "Wurth Electronics Inc")
        (field (name "MFG_PART_#") "7491195501")
      )
      (libsource (lib "eagle-import") (part "TFORM_4_4311_4A4"))
    )
    (comp (ref "U1")
      (value "DG508BEN-T1-GE4")
      (footprint "eagle-import:MINIQFN-16L")
      (fields
        (field (name "MANUFACTURER") "Vishay Siliconix")
        (field (name "MOUSER_PART_#") "78-DG508BEN-T1-GE4")
      )
      (libsource (lib "eagle-import") (part "DG508BEN-T1-GE4"))
    )
    (comp (ref "U2")
      (value "DG508BEN-T1-GE4")
      (footprint "eagle-import:MINIQFN-16L")
      (fields
        (field (name "MANUFACTURER") "Vishay Siliconix")
        (field (name "MOUSER_PART_#") "78-DG508BEN-T1-GE4")
      )
      (libsource (lib "eagle-import") (part "DG508BEN-T1-GE4"))
    )
    (comp (ref "U3")
      (value "74HC595")
      (footprint "eagle-import:16-VFQFN")
      (fields
        (field (name "DIGIKEY_PART_#") "568-2719-1-ND")
        (field (name "MANUFACTURER") "NXP Semiconductors")
        (field (name "MFG_PART_#") "74HC595BQ,115")
      )
      (libsource (lib "eagle-import") (part "74HC595"))
    )
    (comp (ref "U4")
      (value "LTC3805-5IDD")
      (footprint "eagle-import:10-WFDFN")
      (fields
        (field (name "DIGIKEY_PART_#") "LTC3805IDD-5#PBF-ND")
        (field (name "MANUFACTURER") "Linear Technology")
        (field (name "MFG_PART_#") "LTC3805IDD-5#PBF")
      )
      (libsource (lib "eagle-import") (part "LTC3805-5IDD"))
    )
    (comp (ref "U5")
      (value "TC1240A")
      (footprint "eagle-import:SOT-23-6")
      (fields
        (field (name "DIGIKEY_PART_#") "TC1240AECHCT-ND")
        (field (name "MANUFACTURER") "Microchip Technology")
        (field (name "MFG_PART_#") "TC1240AECHTR")
      )
      (libsource (lib "eagle-import") (part "TC1240A"))
    )
    (comp (ref "U6")
      (value "AR30N60PPA-13")
      (footprint "eagle-import:22-VFDFN")
      (fields
        (field (name "DIGIKEY_PART_#") "AR30N60PPA-13DICT-ND")
        (field (name "MANUFACTURER") "Diodes Incorporated")
      )
      (libsource (lib "eagle-import") (part "AR30N60PPA-13"))
    )
    (comp (ref "U10")
      (value "CCR20MA_45V")
      (footprint "eagle-import:SOD-123")
      (fields
        (field (name "DIGIKEY_PART_#") "NSI45020T1GOSCT-ND")
        (field (name "MANUFACTURER") "ON Semiconductor")
        (field (name "MFG_PART_#") "NSI45020T1G")
      )
      (libsource (lib "eagle-import") (part "CCR20MA_45V"))
    )
  )
  (nets
    (net (code "1") (name "/~{EN_S1}") (class "Default")
      (node (ref "Q2") (pin "5") (pinfunction "G_5") (pintype "passive"))
      (node (ref "R10") (pin "2") (pinfunction "2_2") (pintype "passive"))
      (node (ref "U1") (pin "16") (pinfunction "EN_16") (pintype "passive"))
      (node (ref "U3") (pin "15") (pinfunction "Q0_15") (pintype "passive"))
    )
    (net (code "2") (name "/~{OE}") (class "Default")
      (node (ref "R3") (pin "2") (pinfunction "2_2") (pintype "passive"))
      (node (ref "U3") (pin "13") (pinfunction "~{OE}_13") (pintype "passive"))
    )
    (net (code "3") (name "AS0") (class "Default")
      (node (ref "U1") (pin "15") (pinfunction "A0_15") (pintype "passive"))
      (node (ref "U3") (pin "1") (pinfunction "Q1_1") (pintype "passive"))
    )
    (net (code "4") (name "AS1") (class "Default")
      (node (ref "U1") (pin "14") (pinfunction "A1_14") (pintype "passive"))
      (node (ref "U3") (pin "2") (pinfunction "Q2_2") (pintype "passive"))
    )
    (net (code "5") (name "AS2") (class "Default")
      (node (ref "U1") (pin "13") (pinfunction "A2_13") (pintype "passive"))
      (node (ref "U3") (pin "3") (pinfunction "Q3_3") (pintype "passive"))
    )
    (net (code "6") (name "AT0") (class "Default")
      (node (ref "U2") (pin "15") (pinfunction "A0_15") (pintype "passive"))
      (node (ref "U3") (pin "4") (pinfunction "Q4_4") (pintype "passive"))
    )
    (net (code "7") (name "AT1") (class "Default")
      (node (ref "U2") (pin "14") (pinfunction "A1_14") (pintype "passive"))
      (node (ref "U3") (pin "5") (pinfunction "Q5_5") (pintype "passive"))
    )
    (net (code "8") (name "AT2") (class "Default")
      (node (ref "U2") (pin "13") (pinfunction "A2_13") (pintype "passive"))
      (node (ref "U3") (pin "6") (pinfunction "Q6_6") (pintype "passive"))
    )
    (net (code "9") (name "BATT+") (class "Default")
      (node (ref "C7") (pin "2") (pinfunction "2_2") (pintype "passive"))
      (node (ref "D1") (pin "5") (pinfunction "C_5") (pintype "passive"))
      (node (ref "D2") (pin "5") (pinfunction "C_5") (pintype "passive"))
      (node (ref "D2") (pin "6") (pinfunction "C_6") (pintype "passive"))
      (node (ref "RGS+2") (pin "1") (pinfunction "1_1") (pintype "passive"))
      (node (ref "RGS3") (pin "1") (pinfunction "1_1") (pintype "passive"))
      (node (ref "RGS4") (pin "1") (pinfunction "1_1") (pintype "passive"))
      (node (ref "RGS5") (pin "1") (pinfunction "1_1") (pintype "passive"))
      (node (ref "RGS6") (pin "1") (pinfunction "1_1") (pintype "passive"))
      (node (ref "RGT+2") (pin "1") (pinfunction "1_1") (pintype "passive"))
      (node (ref "RGT3") (pin "1") (pinfunction "1_1") (pintype "passive"))
      (node (ref "RGT4") (pin "1") (pinfunction "1_1") (pintype "passive"))
      (node (ref "RGT5") (pin "1") (pinfunction "1_1") (pintype "passive"))
      (node (ref "RGT6") (pin "1") (pinfunction "1_1") (pintype "passive"))
      (node (ref "U1") (pin "11") (pinfunction "V+_11") (pintype "passive"))
      (node (ref "U2") (pin "11") (pinfunction "V+_11") (pintype "passive"))
      (node (ref "U2") (pin "16") (pinfunction "EN_16") (pintype "passive"))
    )
    (net (code "10") (name "BATT-") (class "Default")
      (node (ref "C7") (pin "1") (pinfunction "1_1") (pintype "passive"))
      (node (ref "JP1") (pin "7") (pinfunction "7_7") (pintype "passive"))
      (node (ref "Q14") (pin "S") (pinfunction "S_S") (pintype "passive"))
      (node (ref "Q18") (pin "S") (pinfunction "S_S") (pintype "passive"))
      (node (ref "Q2") (pin "4") (pinfunction "S_4") (pintype "passive"))
      (node (ref "R10") (pin "1") (pinfunction "1_1") (pintype "passive"))
      (node (ref "RGS-2") (pin "1") (pinfunction "1_1") (pintype "passive"))
      (node (ref "RGT-2") (pin "1") (pinfunction "1_1") (pintype "passive"))
      (node (ref "RGT1") (pin "1") (pinfunction "1_1") (pintype "passive"))
      (node (ref "U1") (pin "1") (pinfunction "V-_1") (pintype "passive"))
      (node (ref "U1") (pin "6") (pinfunction "D_6") (pintype "passive"))
      (node (ref "U1") (pin "7") (pinfunction "S8_7") (pintype "passive"))
      (node (ref "U1") (pin "8") (pinfunction "S7_8") (pintype "passive"))
      (node (ref "U1") (pin "9") (pinfunction "S6_9") (pintype "passive"))
      (node (ref "U2") (pin "1") (pinfunction "V-_1") (pintype "passive"))
      (node (ref "U2") (pin "2") (pinfunction "S1_2") (pintype "passive"))
      (node (ref "U2") (pin "6") (pinfunction "D_6") (pintype "passive"))
      (node (ref "U2") (pin "7") (pinfunction "S8_7") (pintype "passive"))
    )
    (net (code "11") (name "C1") (class "Default")
      (node (ref "JP1") (pin "6") (pinfunction "6_6") (pintype "passive"))
      (node (ref "Q11") (pin "D") (pinfunction "D_D") (pintype "passive"))
      (node (ref "Q15") (pin "D") (pinfunction "D_D") (pintype "passive"))
      (node (ref "Q23") (pin "D") (pinfunction "D_D") (pintype "passive"))
      (node (ref "Q27") (pin "D") (pinfunction "D_D") (pintype "passive"))
      (node (ref "U10") (pin "A") (pinfunction "A_A") (pintype "passive"))
    )
    (net (code "12") (name "C2") (class "Default")
      (node (ref "D1") (pin "1") (pinfunction "A_1") (pintype "passive"))
      (node (ref "JP1") (pin "5") (pinfunction "5_5") (pintype "passive"))
      (node (ref "Q21") (pin "D") (pinfunction "D_D") (pintype "passive"))
      (node (ref "Q25") (pin "D") (pinfunction "D_D") (pintype "passive"))
      (node (ref "Q33") (pin "D") (pinfunction "D_D") (pintype "passive"))
      (node (ref "Q37") (pin "D") (pinfunction "D_D") (pintype "passive"))
    )
    (net (code "13") (name "C3") (class "Default")
      (node (ref "D1") (pin "2") (pinfunction "A_2") (pintype "passive"))
      (node (ref "JP1") (pin "4") (pinfunction "4_4") (pintype "passive"))
      (node (ref "Q31") (pin "D") (pinfunction "D_D") (pintype "passive"))
      (node (ref "Q35") (pin "D") (pinfunction "D_D") (pintype "passive"))
      (node (ref "Q43") (pin "D") (pinfunction "D_D") (pintype "passive"))
      (node (ref "Q47") (pin "D") (pinfunction "D_D") (pintype "passive"))
    )
    (net (code "14") (name "C4") (class "Default")
      (node (ref "D1") (pin "3") (pinfunction "A_3") (pintype "passive"))
      (node (ref "JP1") (pin "3") (pinfunction "3_3") (pintype "passive"))
      (node (ref "Q41") (pin "D") (pinfunction "D_D") (pintype "passive"))
      (node (ref "Q45") (pin "D") (pinfunction "D_D") (pintype "passive"))
      (node (ref "Q53") (pin "D") (pinfunction "D_D") (pintype "passive"))
      (node (ref "Q57") (pin "D") (pinfunction "D_D") (pintype "passive"))
    )
    (net (code "15") (name "C4+") (class "Default")
      (node (ref "D1") (pin "4") (pinfunction "A_4") (pintype "passive"))
      (node (ref "D1") (pin "6") (pinfunction "C_6") (pintype "passive"))
      (node (ref "D1") (pin "7") (pinfunction "C_7") (pintype "passive"))
      (node (ref "D1") (pin "8") (pinfunction "C_8") (pintype "passive"))
      (node (ref "Q3") (pin "1") (pinfunction "S_1") (pintype "passive"))
      (node (ref "Q4") (pin "1") (pinfunction "S_1") (pintype "passive"))
      (node (ref "Q4") (pin "4") (pinfunction "S_4") (pintype "passive"))
      (node (ref "RGS1") (pin "1") (pinfunction "1_1") (pintype "passive"))
    )
    (net (code "16") (name "C5") (class "Default")
      (node (ref "D2") (pin "4") (pinfunction "A_4") (pintype "passive"))
      (node (ref "JP1") (pin "2") (pinfunction "2_2") (pintype "passive"))
      (node (ref "Q51") (pin "D") (pinfunction "D_D") (pintype "passive"))
      (node (ref "Q55") (pin "D") (pinfunction "D_D") (pintype "passive"))
      (node (ref "Q64") (pin "S") (pinfunction "S_S") (pintype "passive"))
      (node (ref "Q68") (pin "S") (pinfunction "S_S") (pintype "passive"))
    )
    (net (code "17") (name "C6") (class "Default")
      (node (ref "D2") (pin "3") (pinfunction "A_3") (pintype "passive"))
      (node (ref "JP1") (pin "1") (pinfunction "1_1") (pintype "passive"))
      (node (ref "Q62") (pin "S") (pinfunction "S_S") (pintype "passive"))
      (node (ref "Q66") (pin "S") (pinfunction "S_S") (pintype "passive"))
    )
    (net (code "18") (name "CP") (class "Default")
      (node (ref "U3") (pin "11") (pinfunction "SHCP_11") (pintype "passive"))
      (node (ref "U3") (pin "12") (pinfunction "STCP_12") (pintype "passive"))
    )
    (net (code "19") (name "DS") (class "Default")
      (node (ref "U3") (pin "14") (pinfunction "DS_14") (pintype "passive"))
    )
    (net (code "20") (name "FB") (class "Default")
      (node (ref "R11") (pin "2") (pinfunction "2_2") (pintype "passive"))
    )
    (net (code "21") (name "GS+2") (class "Default")
      (node (ref "Q21") (pin "G") (pinfunction "G_G") (pintype "passive"))
      (node (ref "Q22") (pin "G") (pinfunction "G_G") (pintype "passive"))
      (node (ref "Q3") (pin "2") (pinfunction "G_2") (pintype "passive"))
      (node (ref "RGS+2") (pin "2") (pinfunction "2_2") (pintype "passive"))
      (node (ref "U1") (pin "2") (pinfunction "S1_2") (pintype "passive"))
    )
    (net (code "22") (name "GS-2") (class "Default")
      (node (ref "Q23") (pin "G") (pinfunction "G_G") (pintype "passive"))
      (node (ref "Q24") (pin "G") (pinfunction "G_G") (pintype "passive"))
      (node (ref "Q3") (pin "6") (pinfunction "D_6") (pintype "passive"))
      (node (ref "RGS-2") (pin "2") (pinfunction "2_2") (pintype "passive"))
    )
    (net (code "23") (name "GS1") (class "Default")
      (node (ref "Q11") (pin "G") (pinfunction "G_G") (pintype "passive"))
      (node (ref "Q12") (pin "G") (pinfunction "G_G") (pintype "passive"))
      (node (ref "Q14") (pin "G") (pinfunction "G_G") (pintype "passive"))
      (node (ref "Q2") (pin "3") (pinfunction "D_3") (pintype "passive"))
      (node (ref "RGS1") (pin "2") (pinfunction "2_2") (pintype "passive"))
    )
    (net (code "24") (name "GS3") (class "Default")
      (node (ref "Q31") (pin "G") (pinfunction "G_G") (pintype "passive"))
      (node (ref "Q32") (pin "G") (pinfunction "G_G") (pintype "passive"))
      (node (ref "Q33") (pin "G") (pinfunction "G_G") (pintype "passive"))
      (node (ref "Q34") (pin "G") (pinfunction "G_G") (pintype "passive"))
      (node (ref "RGS3") (pin "2") (pinfunction "2_2") (pintype "passive"))
      (node (ref "U1") (pin "3") (pinfunction "S2_3") (pintype "passive"))
    )
    (net (code "25") (name "GS4") (class "Default")
      (node (ref "Q41") (pin "G") (pinfunction "G_G") (pintype "passive"))
      (node (ref "Q42") (pin "G") (pinfunction "G_G") (pintype "passive"))
      (node (ref "Q43") (pin "G") (pinfunction "G_G") (pintype "passive"))
      (node (ref "Q44") (pin "G") (pinfunction "G_G") (pintype "passive"))
      (node (ref "RGS4") (pin "2") (pinfunction "2_2") (pintype "passive"))
      (node (ref "U1") (pin "4") (pinfunction "S3_4") (pintype "passive"))
    )
    (net (code "26") (name "GS5") (class "Default")
      (node (ref "Q51") (pin "G") (pinfunction "G_G") (pintype "passive"))
      (node (ref "Q52") (pin "G") (pinfunction "G_G") (pintype "passive"))
      (node (ref "Q53") (pin "G") (pinfunction "G_G") (pintype "passive"))
      (node (ref "Q54") (pin "G") (pinfunction "G_G") (pintype "passive"))
      (node (ref "RGS5") (pin "2") (pinfunction "2_2") (pintype "passive"))
      (node (ref "U1") (pin "5") (pinfunction "S4_5") (pintype "passive"))
    )
    (net (code "27") (name "GS6") (class "Default")
      (node (ref "Q62") (pin "G") (pinfunction "G_G") (pintype "passive"))
      (node (ref "Q64") (pin "G") (pinfunction "G_G") (pintype "passive"))
      (node (ref "RGS6") (pin "2") (pinfunction "2_2") (pintype "passive"))
      (node (ref "U1") (pin "10") (pinfunction "S5_10") (pintype "passive"))
    )
    (net (code "28") (name "GT+2") (class "Default")
      (node (ref "Q25") (pin "G") (pinfunction "G_G") (pintype "passive"))
      (node (ref "Q26") (pin "G") (pinfunction "G_G") (pintype "passive"))
      (node (ref "Q4") (pin "5") (pinfunction "G_5") (pintype "passive"))
      (node (ref "RGT+2") (pin "2") (pinfunction "2_2") (pintype "passive"))
      (node (ref "U2") (pin "4") (pinfunction "S3_4") (pintype "passive"))
    )
    (net (code "29") (name "GT-2") (class "Default")
      (node (ref "Q27") (pin "G") (pinfunction "G_G") (pintype "passive"))
      (node (ref "Q28") (pin "G") (pinfunction "G_G") (pintype "passive"))
      (node (ref "Q4") (pin "3") (pinfunction "D_3") (pintype "passive"))
      (node (ref "RGT-2") (pin "2") (pinfunction "2_2") (pintype "passive"))
    )
    (net (code "30") (name "GT1") (class "Default")
      (node (ref "Q15") (pin "G") (pinfunction "G_G") (pintype "passive"))
      (node (ref "Q16") (pin "G") (pinfunction "G_G") (pintype "passive"))
      (node (ref "Q18") (pin "G") (pinfunction "G_G") (pintype "passive"))
      (node (ref "Q4") (pin "6") (pinfunction "D_6") (pintype "passive"))
      (node (ref "RGT1") (pin "2") (pinfunction "2_2") (pintype "passive"))
    )
    (net (code "31") (name "GT3") (class "Default")
      (node (ref "Q35") (pin "G") (pinfunction "G_G") (pintype "passive"))
      (node (ref "Q36") (pin "G") (pinfunction "G_G") (pintype "passive"))
      (node (ref "Q37") (pin "G") (pinfunction "G_G") (pintype "passive"))
      (node (ref "Q38") (pin "G") (pinfunction "G_G") (pintype "passive"))
      (node (ref "RGT3") (pin "2") (pinfunction "2_2") (pintype "passive"))
      (node (ref "U2") (pin "5") (pinfunction "S4_5") (pintype "passive"))
    )
    (net (code "32") (name "GT4") (class "Default")
      (node (ref "Q45") (pin "G") (pinfunction "G_G") (pintype "passive"))
      (node (ref "Q46") (pin "G") (pinfunction "G_G") (pintype "passive"))
      (node (ref "Q47") (pin "G") (pinfunction "G_G") (pintype "passive"))
      (node (ref "Q48") (pin "G") (pinfunction "G_G") (pintype "passive"))
      (node (ref "RGT4") (pin "2") (pinfunction "2_2") (pintype "passive"))
      (node (ref "U2") (pin "10") (pinfunction "S5_10") (pintype "passive"))
    )
    (net (code "33") (name "GT5") (class "Default")
      (node (ref "Q55") (pin "G") (pinfunction "G_G") (pintype "passive"))
      (node (ref "Q56") (pin "G") (pinfunction "G_G") (pintype "passive"))
      (node (ref "Q57") (pin "G") (pinfunction "G_G") (pintype "passive"))
      (node (ref "Q58") (pin "G") (pinfunction "G_G") (pintype "passive"))
      (node (ref "RGT5") (pin "2") (pinfunction "2_2") (pintype "passive"))
      (node (ref "U2") (pin "9") (pinfunction "S6_9") (pintype "passive"))
    )
    (net (code "34") (name "GT6") (class "Default")
      (node (ref "Q66") (pin "G") (pinfunction "G_G") (pintype "passive"))
      (node (ref "Q68") (pin "G") (pinfunction "G_G") (pintype "passive"))
      (node (ref "RGT6") (pin "2") (pinfunction "2_2") (pintype "passive"))
      (node (ref "U2") (pin "8") (pinfunction "S7_8") (pintype "passive"))
    )
    (net (code "35") (name "N$19") (class "Default")
      (node (ref "U3") (pin "9") (pinfunction "Q7S_9") (pintype "passive"))
    )
    (net (code "36") (name "Net-(C4-Pad2)") (class "Default")
      (node (ref "C4") (pin "2") (pinfunction "2_2") (pintype "passive"))
      (node (ref "R7") (pin "1") (pinfunction "1_1") (pintype "passive"))
    )
    (net (code "37") (name "Net-(C9-Pad2)") (class "Default")
      (node (ref "C9") (pin "2") (pinfunction "2_2") (pintype "passive"))
      (node (ref "R13") (pin "1") (pinfunction "1_1") (pintype "passive"))
    )
    (net (code "38") (name "Net-(D3-PadA)") (class "Default")
      (node (ref "D3") (pin "A") (pinfunction "A_A") (pintype "passive"))
      (node (ref "R9") (pin "2") (pinfunction "2_2") (pintype "passive"))
    )
    (net (code "39") (name "Net-(D11-PadA)") (class "Default")
      (node (ref "D11") (pin "A") (pinfunction "A_A") (pintype "passive"))
      (node (ref "D21") (pin "A") (pinfunction "A_A") (pintype "passive"))
      (node (ref "D31") (pin "A") (pinfunction "A_A") (pintype "passive"))
      (node (ref "D41") (pin "A") (pinfunction "A_A") (pintype "passive"))
      (node (ref "D51") (pin "A") (pinfunction "A_A") (pintype "passive"))
      (node (ref "D61") (pin "A") (pinfunction "A_A") (pintype "passive"))
      (node (ref "U10") (pin "C") (pinfunction "C_C") (pintype "passive"))
    )
    (net (code "40") (name "Net-(Q1-PadS)") (class "Default")
      (node (ref "Q1") (pin "S") (pinfunction "S_S") (pintype "passive"))
      (node (ref "R5") (pin "2") (pinfunction "2_2") (pintype "passive"))
      (node (ref "R8") (pin "2") (pinfunction "2_2") (pintype "passive"))
    )
    (net (code "41") (name "Net-(Q4A-G)") (class "Default")
      (node (ref "Q4") (pin "2") (pinfunction "G_2") (pintype "passive"))
      (node (ref "U2") (pin "3") (pinfunction "S2_3") (pintype "passive"))
    )
    (net (code "42") (name "Net-(Q5A-D)") (class "Default")
      (node (ref "C9") (pin "1") (pinfunction "1_1") (pintype "passive"))
      (node (ref "Q5") (pin "6") (pinfunction "D_6") (pintype "passive"))
      (node (ref "R12") (pin "2") (pinfunction "2_2") (pintype "passive"))
    )
    (net (code "43") (name "Net-(Q5A-G)") (class "Default")
      (node (ref "Q1") (pin "G") (pinfunction "G_G") (pintype "passive"))
      (node (ref "Q5") (pin "2") (pinfunction "G_2") (pintype "passive"))
      (node (ref "U4") (pin "6") (pinfunction "GATE_6") (pintype "passive"))
    )
    (net (code "44") (name "Net-(Q5B-G)") (class "Default")
      (node (ref "Q5") (pin "5") (pinfunction "G_5") (pintype "passive"))
      (node (ref "U6") (pin "3") (pinfunction "SFB_3") (pintype "passive"))
    )
    (net (code "45") (name "Net-(Q11-PadS)") (class "Default")
      (node (ref "Q11") (pin "S") (pinfunction "S_S") (pintype "passive"))
      (node (ref "Q12") (pin "S") (pinfunction "S_S") (pintype "passive"))
    )
    (net (code "46") (name "Net-(Q15-PadS)") (class "Default")
      (node (ref "Q15") (pin "S") (pinfunction "S_S") (pintype "passive"))
      (node (ref "Q16") (pin "S") (pinfunction "S_S") (pintype "passive"))
    )
    (net (code "47") (name "Net-(Q21-PadS)") (class "Default")
      (node (ref "Q21") (pin "S") (pinfunction "S_S") (pintype "passive"))
      (node (ref "Q22") (pin "S") (pinfunction "S_S") (pintype "passive"))
    )
    (net (code "48") (name "Net-(Q23-PadS)") (class "Default")
      (node (ref "Q23") (pin "S") (pinfunction "S_S") (pintype "passive"))
      (node (ref "Q24") (pin "S") (pinfunction "S_S") (pintype "passive"))
    )
    (net (code "49") (name "Net-(Q25-PadS)") (class "Default")
      (node (ref "Q25") (pin "S") (pinfunction "S_S") (pintype "passive"))
      (node (ref "Q26") (pin "S") (pinfunction "S_S") (pintype "passive"))
    )
    (net (code "50") (name "Net-(Q27-PadS)") (class "Default")
      (node (ref "Q27") (pin "S") (pinfunction "S_S") (pintype "passive"))
      (node (ref "Q28") (pin "S") (pinfunction "S_S") (pintype "passive"))
    )
    (net (code "51") (name "Net-(Q31-PadS)") (class "Default")
      (node (ref "Q31") (pin "S") (pinfunction "S_S") (pintype "passive"))
      (node (ref "Q32") (pin "S") (pinfunction "S_S") (pintype "passive"))
    )
    (net (code "52") (name "Net-(Q33-PadS)") (class "Default")
      (node (ref "Q33") (pin "S") (pinfunction "S_S") (pintype "passive"))
      (node (ref "Q34") (pin "S") (pinfunction "S_S") (pintype "passive"))
    )
    (net (code "53") (name "Net-(Q35-PadS)") (class "Default")
      (node (ref "Q35") (pin "S") (pinfunction "S_S") (pintype "passive"))
      (node (ref "Q36") (pin "S") (pinfunction "S_S") (pintype "passive"))
    )
    (net (code "54") (name "Net-(Q37-PadS)") (class "Default")
      (node (ref "Q37") (pin "S") (pinfunction "S_S") (pintype "passive"))
      (node (ref "Q38") (pin "S") (pinfunction "S_S") (pintype "passive"))
    )
    (net (code "55") (name "Net-(Q41-PadS)") (class "Default")
      (node (ref "Q41") (pin "S") (pinfunction "S_S") (pintype "passive"))
      (node (ref "Q42") (pin "S") (pinfunction "S_S") (pintype "passive"))
    )
    (net (code "56") (name "Net-(Q43-PadS)") (class "Default")
      (node (ref "Q43") (pin "S") (pinfunction "S_S") (pintype "passive"))
      (node (ref "Q44") (pin "S") (pinfunction "S_S") (pintype "passive"))
    )
    (net (code "57") (name "Net-(Q45-PadS)") (class "Default")
      (node (ref "Q45") (pin "S") (pinfunction "S_S") (pintype "passive"))
      (node (ref "Q46") (pin "S") (pinfunction "S_S") (pintype "passive"))
    )
    (net (code "58") (name "Net-(Q47-PadS)") (class "Default")
      (node (ref "Q47") (pin "S") (pinfunction "S_S") (pintype "passive"))
      (node (ref "Q48") (pin "S") (pinfunction "S_S") (pintype "passive"))
    )
    (net (code "59") (name "Net-(Q51-PadS)") (class "Default")
      (node (ref "Q51") (pin "S") (pinfunction "S_S") (pintype "passive"))
      (node (ref "Q52") (pin "S") (pinfunction "S_S") (pintype "passive"))
    )
    (net (code "60") (name "Net-(Q53-PadS)") (class "Default")
      (node (ref "Q53") (pin "S") (pinfunction "S_S") (pintype "passive"))
      (node (ref "Q54") (pin "S") (pinfunction "S_S") (pintype "passive"))
    )
    (net (code "61") (name "Net-(Q55-PadS)") (class "Default")
      (node (ref "Q55") (pin "S") (pinfunction "S_S") (pintype "passive"))
      (node (ref "Q56") (pin "S") (pinfunction "S_S") (pintype "passive"))
    )
    (net (code "62") (name "Net-(Q57-PadS)") (class "Default")
      (node (ref "Q57") (pin "S") (pinfunction "S_S") (pintype "passive"))
      (node (ref "Q58") (pin "S") (pinfunction "S_S") (pintype "passive"))
    )
    (net (code "63") (name "Net-(T1-5)") (class "Default")
      (node (ref "Q1") (pin "D") (pinfunction "D_D") (pintype "passive"))
      (node (ref "T1") (pin "6") (pinfunction "7_6") (pintype "passive"))
      (node (ref "T1") (pin "7") (pinfunction "5_7") (pintype "passive"))
    )
    (net (code "64") (name "Net-(T1-Pad1)") (class "Default")
      (node (ref "T1") (pin "1") (pinfunction "1_1") (pintype "passive"))
      (node (ref "U6") (pin "12-17") (pinfunction "VD_12-17") (pintype "passive"))
      (node (ref "U6") (pin "VD") (pinfunction "VD_VD") (pintype "passive"))
    )
    (net (code "65") (name "Net-(U3-~{MR})") (class "Default")
      (node (ref "R4") (pin "2") (pinfunction "2_2") (pintype "passive"))
      (node (ref "U3") (pin "10") (pinfunction "~{MR}_10") (pintype "passive"))
    )
    (net (code "66") (name "Net-(U4-FB)") (class "Default")
      (node (ref "D4") (pin "C") (pinfunction "C_C") (pintype "passive"))
      (node (ref "R11") (pin "1") (pinfunction "1_1") (pintype "passive"))
      (node (ref "U4") (pin "3") (pinfunction "FB_3") (pintype "passive"))
    )
    (net (code "67") (name "Net-(U4-FS)") (class "Default")
      (node (ref "R6") (pin "2") (pinfunction "2_2") (pintype "passive"))
      (node (ref "U4") (pin "5") (pinfunction "FS_5") (pintype "passive"))
    )
    (net (code "68") (name "Net-(U4-I_SENSE)") (class "Default")
      (node (ref "R8") (pin "1") (pinfunction "1_1") (pintype "passive"))
      (node (ref "U4") (pin "9") (pinfunction "I_SENSE_9") (pintype "passive"))
    )
    (net (code "69") (name "Net-(U4-I_TH)") (class "Default")
      (node (ref "R7") (pin "2") (pinfunction "2_2") (pintype "passive"))
      (node (ref "U4") (pin "2") (pinfunction "I_TH_2") (pintype "passive"))
    )
    (net (code "70") (name "Net-(U4-VCC)") (class "Default")
      (node (ref "C2") (pin "2") (pinfunction "2_2") (pintype "passive"))
      (node (ref "C3") (pin "1") (pinfunction "1_1") (pintype "passive"))
      (node (ref "R12") (pin "1") (pinfunction "1_1") (pintype "passive"))
      (node (ref "U4") (pin "7") (pinfunction "VCC_7") (pintype "power_in"))
      (node (ref "U5") (pin "5") (pinfunction "VOUT_5") (pintype "power_in"))
    )
    (net (code "71") (name "Net-(U5-C+)") (class "Default")
      (node (ref "C1") (pin "2") (pinfunction "2_2") (pintype "passive"))
      (node (ref "U5") (pin "6") (pinfunction "C+_6") (pintype "passive"))
    )
    (net (code "72") (name "Net-(U5-C-)") (class "Default")
      (node (ref "C1") (pin "1") (pinfunction "1_1") (pintype "passive"))
      (node (ref "U5") (pin "3") (pinfunction "C-_3") (pintype "passive"))
    )
    (net (code "73") (name "Net-(U6-SYNC)") (class "Default")
      (node (ref "R13") (pin "2") (pinfunction "2_2") (pintype "passive"))
      (node (ref "U6") (pin "19") (pinfunction "SYNC_19") (pintype "passive"))
    )
    (net (code "74") (name "Net-(U6-TOFF{slash}EN)") (class "Default")
      (node (ref "R15") (pin "2") (pinfunction "2_2") (pintype "passive"))
      (node (ref "U6") (pin "2") (pinfunction "TOFF/EN_2") (pintype "passive"))
    )
    (net (code "75") (name "Net-(U6-TON)") (class "Default")
      (node (ref "R14") (pin "2") (pinfunction "2_2") (pintype "passive"))
      (node (ref "U6") (pin "1") (pinfunction "TON_1") (pintype "passive"))
    )
    (net (code "76") (name "OPTO_A") (class "Default")
      (node (ref "R17") (pin "1") (pinfunction "1_1") (pintype "passive"))
    )
    (net (code "77") (name "OPTO_C") (class "Default")
      (node (ref "Q5") (pin "3") (pinfunction "D_3") (pintype "passive"))
      (node (ref "R18") (pin "2") (pinfunction "2_2") (pintype "passive"))
    )
    (net (code "78") (name "RUN_REG") (class "Default")
      (node (ref "U3") (pin "7") (pinfunction "Q7_7") (pintype "passive"))
      (node (ref "U4") (pin "4") (pinfunction "RUN_4") (pintype "passive"))
    )
    (net (code "79") (name "S+") (class "Default")
      (node (ref "C5") (pin "2") (pinfunction "2_2") (pintype "passive"))
      (node (ref "Q12") (pin "D") (pinfunction "D_D") (pintype "passive"))
      (node (ref "Q22") (pin "D") (pinfunction "D_D") (pintype "passive"))
      (node (ref "Q32") (pin "D") (pinfunction "D_D") (pintype "passive"))
      (node (ref "Q42") (pin "D") (pinfunction "D_D") (pintype "passive"))
      (node (ref "Q52") (pin "D") (pinfunction "D_D") (pintype "passive"))
      (node (ref "Q62") (pin "D") (pinfunction "D_D") (pintype "passive"))
      (node (ref "R1") (pin "2") (pinfunction "2_2") (pintype "passive"))
      (node (ref "R9") (pin "1") (pinfunction "1_1") (pintype "passive"))
      (node (ref "T1") (pin "10") (pinfunction "6_10") (pintype "passive"))
      (node (ref "T1") (pin "9") (pinfunction "8_9") (pintype "passive"))
    )
    (net (code "80") (name "S-") (class "Default")
      (node (ref "C2") (pin "1") (pinfunction "1_1") (pintype "passive"))
      (node (ref "C4") (pin "1") (pinfunction "1_1") (pintype "passive"))
      (node (ref "C5") (pin "1") (pinfunction "1_1") (pintype "passive"))
      (node (ref "C6") (pin "1") (pinfunction "1_1") (pintype "passive"))
      (node (ref "C8") (pin "1") (pinfunction "1_1") (pintype "passive"))
      (node (ref "D4") (pin "A") (pinfunction "A_A") (pintype "passive"))
      (node (ref "Q14") (pin "D") (pinfunction "D_D") (pintype "passive"))
      (node (ref "Q24") (pin "D") (pinfunction "D_D") (pintype "passive"))
      (node (ref "Q34") (pin "D") (pinfunction "D_D") (pintype "passive"))
      (node (ref "Q44") (pin "D") (pinfunction "D_D") (pintype "passive"))
      (node (ref "Q5") (pin "1") (pinfunction "S_1") (pintype "passive"))
      (node (ref "Q54") (pin "D") (pinfunction "D_D") (pintype "passive"))
      (node (ref "Q64") (pin "D") (pinfunction "D_D") (pintype "passive"))
      (node (ref "R1") (pin "1") (pinfunction "1_1") (pintype "passive"))
      (node (ref "R4") (pin "1") (pinfunction "1_1") (pintype "passive"))
      (node (ref "R5") (pin "1") (pinfunction "1_1") (pintype "passive"))
      (node (ref "R6") (pin "1") (pinfunction "1_1") (pintype "passive"))
      (node (ref "U1") (pin "12") (pinfunction "GND_12") (pintype "passive"))
      (node (ref "U2") (pin "12") (pinfunction "GND_12") (pintype "passive"))
      (node (ref "U3") (pin "8") (pinfunction "GND_8") (pintype "passive"))
      (node (ref "U3") (pin "PAD") (pinfunction "GND_PAD") (pintype "passive"))
      (node (ref "U4") (pin "10") (pinfunction "SYNC_10") (pintype "passive"))
      (node (ref "U4") (pin "8") (pinfunction "OC_8") (pintype "passive"))
      (node (ref "U4") (pin "PAD") (pinfunction "GND_PAD") (pintype "power_in"))
      (node (ref "U5") (pin "2") (pinfunction "GND_2") (pintype "power_in"))
      (node (ref "U5") (pin "4") (pinfunction "SHDN_4") (pintype "passive"))
    )
    (net (code "81") (name "T+") (class "Default")
      (node (ref "C10") (pin "2") (pinfunction "2_2") (pintype "passive"))
      (node (ref "Q16") (pin "D") (pinfunction "D_D") (pintype "passive"))
      (node (ref "Q26") (pin "D") (pinfunction "D_D") (pintype "passive"))
      (node (ref "Q36") (pin "D") (pinfunction "D_D") (pintype "passive"))
      (node (ref "Q46") (pin "D") (pinfunction "D_D") (pintype "passive"))
      (node (ref "Q56") (pin "D") (pinfunction "D_D") (pintype "passive"))
      (node (ref "Q66") (pin "D") (pinfunction "D_D") (pintype "passive"))
      (node (ref "R17") (pin "2") (pinfunction "2_2") (pintype "passive"))
      (node (ref "R2") (pin "2") (pinfunction "2_2") (pintype "passive"))
      (node (ref "T1") (pin "3") (pinfunction "2_3") (pintype "passive"))
      (node (ref "U6") (pin "22") (pinfunction "VCC_22") (pintype "power_in"))
    )
    (net (code "82") (name "T-") (class "Default")
      (node (ref "C10") (pin "1") (pinfunction "1_1") (pintype "passive"))
      (node (ref "Q18") (pin "D") (pinfunction "D_D") (pintype "passive"))
      (node (ref "Q28") (pin "D") (pinfunction "D_D") (pintype "passive"))
      (node (ref "Q38") (pin "D") (pinfunction "D_D") (pintype "passive"))
      (node (ref "Q48") (pin "D") (pinfunction "D_D") (pintype "passive"))
      (node (ref "Q5") (pin "4") (pinfunction "S_4") (pintype "passive"))
      (node (ref "Q58") (pin "D") (pinfunction "D_D") (pintype "passive"))
      (node (ref "Q68") (pin "D") (pinfunction "D_D") (pintype "passive"))
      (node (ref "R14") (pin "1") (pinfunction "1_1") (pintype "passive"))
      (node (ref "R15") (pin "1") (pinfunction "1_1") (pintype "passive"))
      (node (ref "R18") (pin "1") (pinfunction "1_1") (pintype "passive"))
      (node (ref "R2") (pin "1") (pinfunction "1_1") (pintype "passive"))
      (node (ref "T1") (pin "4") (pinfunction "3_4") (pintype "passive"))
      (node (ref "U6") (pin "21") (pinfunction "GND_21") (pintype "power_in"))
      (node (ref "U6") (pin "5") (pinfunction "VS_5") (pintype "passive"))
      (node (ref "U6") (pin "6-11") (pinfunction "VS_6-11") (pintype "passive"))
      (node (ref "U6") (pin "GND") (pinfunction "GND_GND") (pintype "power_in"))
    )
    (net (code "83") (name "VCC") (class "Default")
      (node (ref "C3") (pin "2") (pinfunction "2_2") (pintype "passive"))
      (node (ref "C6") (pin "2") (pinfunction "2_2") (pintype "passive"))
      (node (ref "C8") (pin "2") (pinfunction "2_2") (pintype "passive"))
      (node (ref "D3") (pin "C") (pinfunction "C_C") (pintype "passive"))
      (node (ref "R3") (pin "1") (pinfunction "1_1") (pintype "passive"))
      (node (ref "U3") (pin "16") (pinfunction "VCC_16") (pintype "passive"))
      (node (ref "U5") (pin "1") (pinfunction "VIN_1") (pintype "power_in"))
    )
    (net (code "84") (name "unconnected-(D11-PadC)") (class "Default")
      (node (ref "D11") (pin "C") (pinfunction "C_C") (pintype "passive"))
    )
    (net (code "85") (name "unconnected-(D21-PadC)") (class "Default")
      (node (ref "D21") (pin "C") (pinfunction "C_C") (pintype "passive"))
    )
    (net (code "86") (name "unconnected-(D31-PadC)") (class "Default")
      (node (ref "D31") (pin "C") (pinfunction "C_C") (pintype "passive"))
    )
    (net (code "87") (name "unconnected-(D41-PadC)") (class "Default")
      (node (ref "D41") (pin "C") (pinfunction "C_C") (pintype "passive"))
    )
    (net (code "88") (name "unconnected-(D51-PadC)") (class "Default")
      (node (ref "D51") (pin "C") (pinfunction "C_C") (pintype "passive"))
    )
    (net (code "89") (name "unconnected-(D61-PadC)") (class "Default")
      (node (ref "D61") (pin "C") (pinfunction "C_C") (pintype "passive"))
    )
    (net (code "90") (name "unconnected-(Q2A-D-Pad6)") (class "Default")
      (node (ref "Q2") (pin "6") (pinfunction "D_6") (pintype "passive"))
    )
    (net (code "91") (name "unconnected-(Q2A-G-Pad2)") (class "Default")
      (node (ref "Q2") (pin "2") (pinfunction "G_2") (pintype "passive"))
    )
    (net (code "92") (name "unconnected-(Q2A-S-Pad1)") (class "Default")
      (node (ref "Q2") (pin "1") (pinfunction "S_1") (pintype "passive"))
    )
    (net (code "93") (name "unconnected-(T1-4-Pad5)") (class "Default")
      (node (ref "T1") (pin "5") (pinfunction "4_5") (pintype "passive"))
    )
    (net (code "94") (name "unconnected-(U4-SSFLT-Pad1)") (class "Default")
      (node (ref "U4") (pin "1") (pinfunction "SSFLT_1") (pintype "passive"))
    )
  )
)
